# Main.net
KiCad netlist of a schematic drawn in Altium Designer
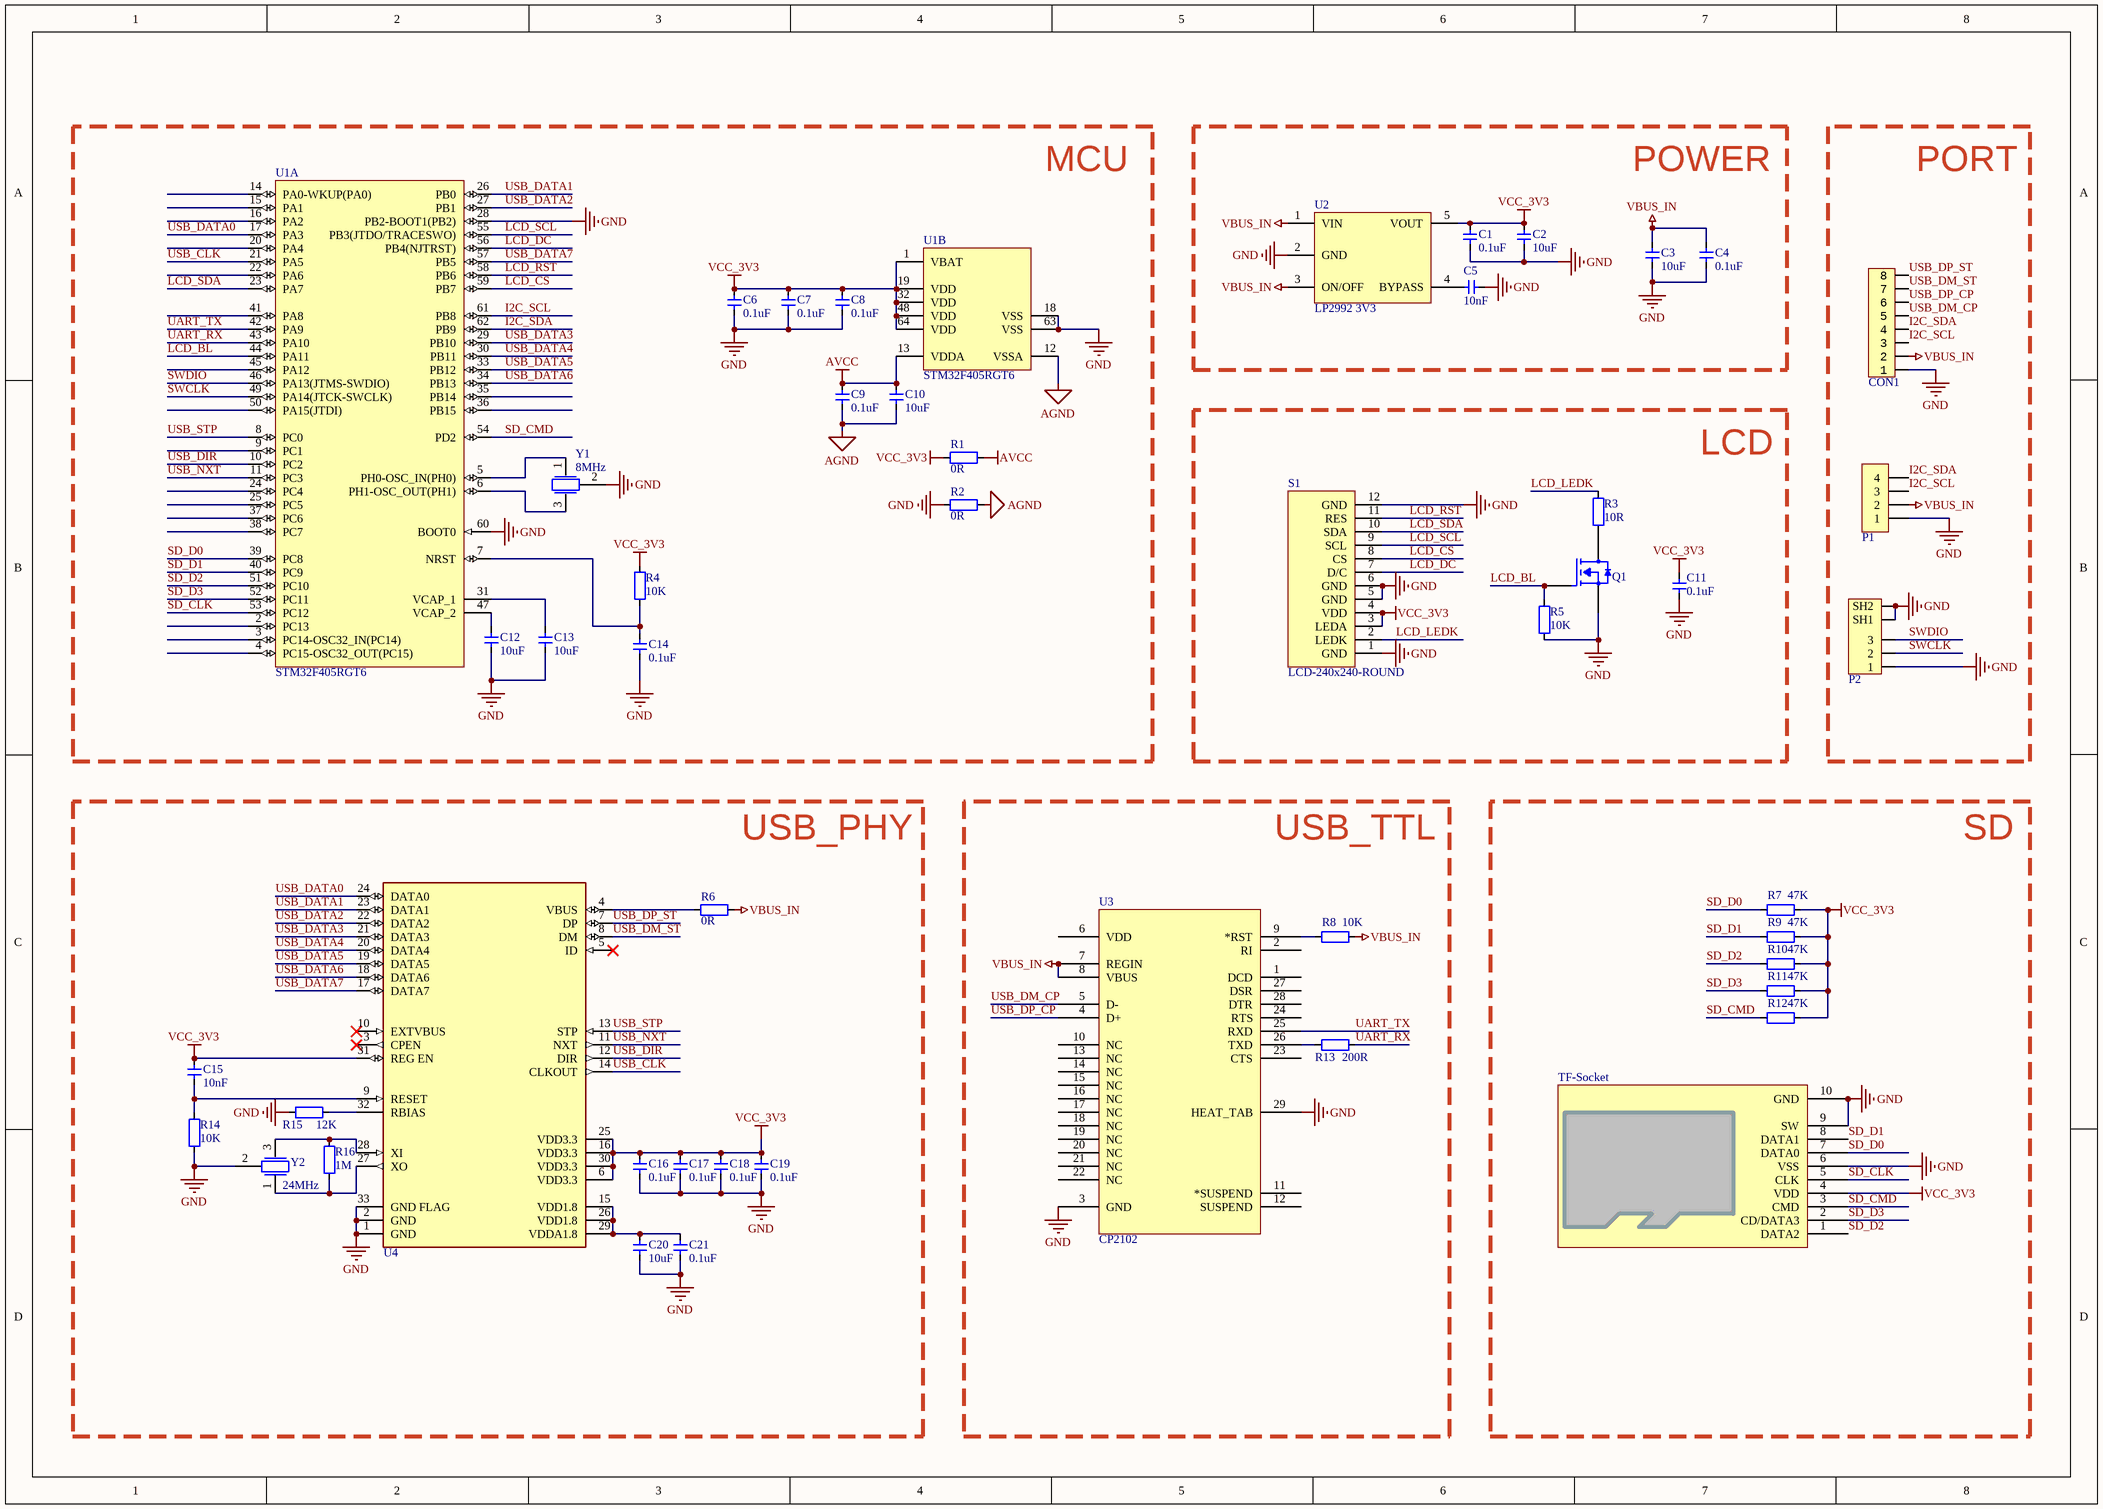
[diagram p0: Main.SchDoc]

(export (version "E")
  (design (tool "Eeschema 10.0.6"))
  (components
    (comp (ref "C1")
      (value "0.1uF")
      (footprint "CAP_0402")
      (description "Capacitor")
      (libsource (lib "MyPcbLib") (part "电容-0402"))
    )
    (comp (ref "C2")
      (value "10uF")
      (footprint "CAP_0402")
      (description "Capacitor")
      (libsource (lib "MyPcbLib") (part "电容-0402"))
    )
    (comp (ref "C3")
      (value "10uF")
      (footprint "CAP_0402")
      (description "Capacitor")
      (libsource (lib "MyPcbLib") (part "电容-0402"))
    )
    (comp (ref "C4")
      (value "0.1uF")
      (footprint "CAP_0402")
      (description "Capacitor")
      (libsource (lib "MyPcbLib") (part "电容-0402"))
    )
    (comp (ref "C5")
      (value "10nF")
      (footprint "CAP_0402")
      (description "Capacitor")
      (libsource (lib "MyPcbLib") (part "电容-0402"))
    )
    (comp (ref "C6")
      (value "0.1uF")
      (footprint "CAP_0402")
      (description "Capacitor")
      (libsource (lib "MyPcbLib") (part "电容-0402"))
    )
    (comp (ref "C7")
      (value "0.1uF")
      (footprint "CAP_0402")
      (description "Capacitor")
      (libsource (lib "MyPcbLib") (part "电容-0402"))
    )
    (comp (ref "C8")
      (value "0.1uF")
      (footprint "CAP_0402")
      (description "Capacitor")
      (libsource (lib "MyPcbLib") (part "电容-0402"))
    )
    (comp (ref "C9")
      (value "0.1uF")
      (footprint "CAP_0402")
      (description "Capacitor")
      (libsource (lib "MyPcbLib") (part "电容-0402"))
    )
    (comp (ref "C10")
      (value "10uF")
      (footprint "CAP_0402")
      (description "Capacitor")
      (libsource (lib "MyPcbLib") (part "电容-0402"))
    )
    (comp (ref "C11")
      (value "0.1uF")
      (footprint "CAP_0402")
      (description "Capacitor")
      (libsource (lib "MyPcbLib") (part "电容-0402"))
    )
    (comp (ref "C12")
      (value "10uF")
      (footprint "CAP_0402")
      (description "Capacitor")
      (libsource (lib "MyPcbLib") (part "电容-0402"))
    )
    (comp (ref "C13")
      (value "10uF")
      (footprint "CAP_0402")
      (description "Capacitor")
      (libsource (lib "MyPcbLib") (part "电容-0402"))
    )
    (comp (ref "C14")
      (value "0.1uF")
      (footprint "CAP_0402")
      (description "Capacitor")
      (libsource (lib "MyPcbLib") (part "电容-0402"))
    )
    (comp (ref "C15")
      (value "10nF")
      (footprint "CAP_0402")
      (description "Capacitor")
      (libsource (lib "MyPcbLib") (part "电容-0402"))
    )
    (comp (ref "C16")
      (value "0.1uF")
      (footprint "CAP_0402")
      (description "Capacitor")
      (libsource (lib "MyPcbLib") (part "电容-0402"))
    )
    (comp (ref "C17")
      (value "0.1uF")
      (footprint "CAP_0402")
      (description "Capacitor")
      (libsource (lib "MyPcbLib") (part "电容-0402"))
    )
    (comp (ref "C18")
      (value "0.1uF")
      (footprint "CAP_0402")
      (description "Capacitor")
      (libsource (lib "MyPcbLib") (part "电容-0402"))
    )
    (comp (ref "C19")
      (value "0.1uF")
      (footprint "CAP_0402")
      (description "Capacitor")
      (libsource (lib "MyPcbLib") (part "电容-0402"))
    )
    (comp (ref "C20")
      (value "10uF")
      (footprint "CAP_0402")
      (description "Capacitor")
      (libsource (lib "MyPcbLib") (part "电容-0402"))
    )
    (comp (ref "C21")
      (value "0.1uF")
      (footprint "CAP_0402")
      (description "Capacitor")
      (libsource (lib "MyPcbLib") (part "电容-0402"))
    )
    (comp (ref "CON1")
      (value "FFC_0.5_8")
      (footprint "FFC_0.5_8")
      (description "FFC")
      (libsource (lib "KitSprout") (part "FFC_0.5_8"))
    )
    (comp (ref "P1")
      (value "CON-4P")
      (footprint "FPC0.5-WT-4P")
      (description "4P连接器")
      (libsource (lib "4.9 - 0.5mm连接器(FPC0.5)") (part "Header 4"))
    )
    (comp (ref "P2")
      (value "SH1.0-3P-STAND")
      (footprint "SH1.0-3P-STAND")
      (description "Header")
      (libsource (lib "MyPcbLib") (part "SH1.0-3P-STAND"))
    )
    (comp (ref "Q1")
      (value "AO3400A")
      (footprint "SOT23-3")
      (description "N-MOS")
      (libsource (lib "MyPcbLib") (part "AO3400A"))
    )
    (comp (ref "R1")
      (value "0R")
      (footprint "RES_0402")
      (description "Resistor")
      (libsource (lib "MyPcbLib") (part "电阻-0402"))
    )
    (comp (ref "R2")
      (value "0R")
      (footprint "RES_0402")
      (description "Resistor")
      (libsource (lib "MyPcbLib") (part "电阻-0402"))
    )
    (comp (ref "R3")
      (value "10R")
      (footprint "RES_0402")
      (description "Resistor")
      (libsource (lib "") (part "电阻-0402_1"))
    )
    (comp (ref "R4")
      (value "10K")
      (footprint "RES_0402")
      (description "Resistor")
      (libsource (lib "") (part "电阻-0402_1"))
    )
    (comp (ref "R5")
      (value "10K")
      (footprint "RES_0402")
      (description "Resistor")
      (libsource (lib "") (part "电阻-0402_1"))
    )
    (comp (ref "R6")
      (value "0R")
      (footprint "RES_0402")
      (description "Resistor")
      (libsource (lib "MyPcbLib") (part "电阻-0402"))
    )
    (comp (ref "R7")
      (value "47K")
      (footprint "RES_0402")
      (description "Resistor")
      (libsource (lib "MyPcbLib") (part "电阻-0402"))
    )
    (comp (ref "R8")
      (value "10K")
      (footprint "RES_0402")
      (description "Resistor")
      (libsource (lib "MyPcbLib") (part "电阻-0402"))
    )
    (comp (ref "R9")
      (value "47K")
      (footprint "RES_0402")
      (description "Resistor")
      (libsource (lib "MyPcbLib") (part "电阻-0402"))
    )
    (comp (ref "R10")
      (value "47K")
      (footprint "RES_0402")
      (description "Resistor")
      (libsource (lib "MyPcbLib") (part "电阻-0402"))
    )
    (comp (ref "R11")
      (value "47K")
      (footprint "RES_0402")
      (description "Resistor")
      (libsource (lib "MyPcbLib") (part "电阻-0402"))
    )
    (comp (ref "R12")
      (value "47K")
      (footprint "RES_0402")
      (description "Resistor")
      (libsource (lib "MyPcbLib") (part "电阻-0402"))
    )
    (comp (ref "R13")
      (value "200R")
      (footprint "RES_0402")
      (description "Resistor")
      (libsource (lib "MyPcbLib") (part "电阻-0402"))
    )
    (comp (ref "R14")
      (value "10K")
      (footprint "RES_0402")
      (description "Resistor")
      (libsource (lib "") (part "电阻-0402_2"))
    )
    (comp (ref "R15")
      (value "12K")
      (footprint "RES_0402")
      (description "Resistor")
      (libsource (lib "MyPcbLib") (part "电阻-0402"))
    )
    (comp (ref "R16")
      (value "1M")
      (footprint "RES_0402")
      (description "Resistor")
      (libsource (lib "") (part "电阻-0402_2"))
    )
    (comp (ref "S1")
      (value "LCD-240x240-ROUND")
      (footprint "LCD-240x240-ROUND")
      (description "显示屏")
      (libsource (lib "mLib") (part "LCD-240x240-ROUND"))
    )
    (comp (ref "TF-Socket")
      (value "TF")
      (footprint "TF-Card-Amphenol with TF")
      (description "8脚自弹")
      (libsource (lib "MyPcbLib") (part "TF卡座"))
    )
    (comp (ref "U1")
      (value "STM32F405RGT6")
      (footprint "LQFP-64_N")
      (fields (field (name "MANUFACTURER") "STMicroelectronics"))
      (libsource (lib "STMicroelectronics STM32 F4") (part "STM32F405RGT6"))
    )
    (comp (ref "U2")
      (value "LP2992 3V3")
      (footprint "SOT23-5")
      (description "LDO")
      (libsource (lib "MyPcbLib") (part "LP2992"))
    )
    (comp (ref "U3")
      (value "CP2102")
      (footprint "QFN-28")
      (description "USB转TTL")
      (libsource (lib "mLib") (part "CP2102"))
    )
    (comp (ref "U4")
      (value "USB3300-EZK-TR")
      (footprint "QFN-32")
      (libsource (lib "mLib") (part "USB3300-EZK-TR"))
    )
    (comp (ref "Y1")
      (value "8MHz")
      (footprint "晶振-3P")
      (description "村田贴片")
      (libsource (lib "MyPcbLib") (part "晶振-3Pin"))
    )
    (comp (ref "Y2")
      (value "24MHz")
      (footprint "晶振-3P")
      (description "村田贴片")
      (libsource (lib "MyPcbLib") (part "晶振-3Pin"))
    )
  )
  (nets
    (net (code "1") (name "/I2C_SCL") (class "Default")
      (node (ref "CON1") (pin "3") (pinfunction "3_3") (pintype "passive"))
      (node (ref "P1") (pin "3") (pinfunction "3_3") (pintype "passive"))
      (node (ref "U1") (pin "61") (pinfunction "PB8_61") (pintype "bidirectional"))
    )
    (net (code "2") (name "/I2C_SDA") (class "Default")
      (node (ref "CON1") (pin "4") (pinfunction "4_4") (pintype "passive"))
      (node (ref "P1") (pin "4") (pinfunction "4_4") (pintype "passive"))
      (node (ref "U1") (pin "62") (pinfunction "PB9_62") (pintype "bidirectional"))
    )
    (net (code "3") (name "/LCD_BL") (class "Default")
      (node (ref "Q1") (pin "1") (pinfunction "G_1") (pintype "passive"))
      (node (ref "R5") (pin "2") (pinfunction "2_2") (pintype "passive"))
      (node (ref "U1") (pin "44") (pinfunction "PA11_44") (pintype "bidirectional"))
    )
    (net (code "4") (name "/LCD_CS") (class "Default")
      (node (ref "S1") (pin "8") (pinfunction "CS_8") (pintype "passive"))
      (node (ref "U1") (pin "59") (pinfunction "PB7_59") (pintype "bidirectional"))
    )
    (net (code "5") (name "/LCD_DC") (class "Default")
      (node (ref "S1") (pin "7") (pinfunction "D/C_7") (pintype "passive"))
      (node (ref "U1") (pin "56") (pinfunction "PB4(NJTRST)_56") (pintype "bidirectional"))
    )
    (net (code "6") (name "/LCD_LEDK") (class "Default")
      (node (ref "R3") (pin "2") (pinfunction "2_2") (pintype "passive"))
      (node (ref "S1") (pin "2") (pinfunction "LEDK_2") (pintype "passive"))
    )
    (net (code "7") (name "/LCD_RST") (class "Default")
      (node (ref "S1") (pin "11") (pinfunction "RES_11") (pintype "passive"))
      (node (ref "U1") (pin "58") (pinfunction "PB6_58") (pintype "bidirectional"))
    )
    (net (code "8") (name "/LCD_SCL") (class "Default")
      (node (ref "S1") (pin "9") (pinfunction "SCL_9") (pintype "passive"))
      (node (ref "U1") (pin "55") (pinfunction "PB3(JTDO/TRACESWO)_55") (pintype "bidirectional"))
    )
    (net (code "9") (name "/LCD_SDA") (class "Default")
      (node (ref "S1") (pin "10") (pinfunction "SDA_10") (pintype "passive"))
      (node (ref "U1") (pin "23") (pinfunction "PA7_23") (pintype "bidirectional"))
    )
    (net (code "10") (name "/SD_CLK") (class "Default")
      (node (ref "TF-Socket") (pin "5") (pinfunction "CLK_5") (pintype "passive"))
      (node (ref "U1") (pin "53") (pinfunction "PC12_53") (pintype "bidirectional"))
    )
    (net (code "11") (name "/SD_CMD") (class "Default")
      (node (ref "R12") (pin "2") (pinfunction "2_2") (pintype "passive"))
      (node (ref "TF-Socket") (pin "3") (pinfunction "CMD_3") (pintype "passive"))
      (node (ref "U1") (pin "54") (pinfunction "PD2_54") (pintype "bidirectional"))
    )
    (net (code "12") (name "/SD_D0") (class "Default")
      (node (ref "R7") (pin "2") (pinfunction "2_2") (pintype "passive"))
      (node (ref "TF-Socket") (pin "7") (pinfunction "DATA0_7") (pintype "passive"))
      (node (ref "U1") (pin "39") (pinfunction "PC8_39") (pintype "bidirectional"))
    )
    (net (code "13") (name "/SD_D1") (class "Default")
      (node (ref "R9") (pin "2") (pinfunction "2_2") (pintype "passive"))
      (node (ref "TF-Socket") (pin "8") (pinfunction "DATA1_8") (pintype "passive"))
      (node (ref "U1") (pin "40") (pinfunction "PC9_40") (pintype "bidirectional"))
    )
    (net (code "14") (name "/SD_D2") (class "Default")
      (node (ref "R10") (pin "2") (pinfunction "2_2") (pintype "passive"))
      (node (ref "TF-Socket") (pin "1") (pinfunction "DATA2_1") (pintype "passive"))
      (node (ref "U1") (pin "51") (pinfunction "PC10_51") (pintype "bidirectional"))
    )
    (net (code "15") (name "/SD_D3") (class "Default")
      (node (ref "R11") (pin "2") (pinfunction "2_2") (pintype "passive"))
      (node (ref "TF-Socket") (pin "2") (pinfunction "CD/DATA3_2") (pintype "passive"))
      (node (ref "U1") (pin "52") (pinfunction "PC11_52") (pintype "bidirectional"))
    )
    (net (code "16") (name "/SWCLK") (class "Default")
      (node (ref "P2") (pin "2") (pinfunction "2_2") (pintype "passive"))
      (node (ref "U1") (pin "49") (pinfunction "PA14(JTCK-SWCLK)_49") (pintype "bidirectional"))
    )
    (net (code "17") (name "/SWDIO") (class "Default")
      (node (ref "P2") (pin "3") (pinfunction "3_3") (pintype "passive"))
      (node (ref "U1") (pin "46") (pinfunction "PA13(JTMS-SWDIO)_46") (pintype "bidirectional"))
    )
    (net (code "18") (name "/UART_RX") (class "Default")
      (node (ref "R13") (pin "1") (pinfunction "1_1") (pintype "passive"))
      (node (ref "U1") (pin "43") (pinfunction "PA10_43") (pintype "bidirectional"))
    )
    (net (code "19") (name "/UART_TX") (class "Default")
      (node (ref "U1") (pin "42") (pinfunction "PA9_42") (pintype "bidirectional"))
      (node (ref "U3") (pin "25") (pinfunction "RXD_25") (pintype "passive"))
    )
    (net (code "20") (name "/USB_CLK") (class "Default")
      (node (ref "U1") (pin "21") (pinfunction "PA5_21") (pintype "bidirectional"))
      (node (ref "U4") (pin "14") (pinfunction "CLKOUT_14") (pintype "output"))
    )
    (net (code "21") (name "/USB_DATA0") (class "Default")
      (node (ref "U1") (pin "17") (pinfunction "PA3_17") (pintype "bidirectional"))
      (node (ref "U4") (pin "24") (pinfunction "DATA0_24") (pintype "bidirectional"))
    )
    (net (code "22") (name "/USB_DATA1") (class "Default")
      (node (ref "U1") (pin "26") (pinfunction "PB0_26") (pintype "bidirectional"))
      (node (ref "U4") (pin "23") (pinfunction "DATA1_23") (pintype "bidirectional"))
    )
    (net (code "23") (name "/USB_DATA2") (class "Default")
      (node (ref "U1") (pin "27") (pinfunction "PB1_27") (pintype "bidirectional"))
      (node (ref "U4") (pin "22") (pinfunction "DATA2_22") (pintype "bidirectional"))
    )
    (net (code "24") (name "/USB_DATA3") (class "Default")
      (node (ref "U1") (pin "29") (pinfunction "PB10_29") (pintype "bidirectional"))
      (node (ref "U4") (pin "21") (pinfunction "DATA3_21") (pintype "bidirectional"))
    )
    (net (code "25") (name "/USB_DATA4") (class "Default")
      (node (ref "U1") (pin "30") (pinfunction "PB11_30") (pintype "bidirectional"))
      (node (ref "U4") (pin "20") (pinfunction "DATA4_20") (pintype "bidirectional"))
    )
    (net (code "26") (name "/USB_DATA5") (class "Default")
      (node (ref "U1") (pin "33") (pinfunction "PB12_33") (pintype "bidirectional"))
      (node (ref "U4") (pin "19") (pinfunction "DATA5_19") (pintype "bidirectional"))
    )
    (net (code "27") (name "/USB_DATA6") (class "Default")
      (node (ref "U1") (pin "34") (pinfunction "PB13_34") (pintype "bidirectional"))
      (node (ref "U4") (pin "18") (pinfunction "DATA6_18") (pintype "bidirectional"))
    )
    (net (code "28") (name "/USB_DATA7") (class "Default")
      (node (ref "U1") (pin "57") (pinfunction "PB5_57") (pintype "bidirectional"))
      (node (ref "U4") (pin "17") (pinfunction "DATA7_17") (pintype "bidirectional"))
    )
    (net (code "29") (name "/USB_DIR") (class "Default")
      (node (ref "U1") (pin "10") (pinfunction "PC2_10") (pintype "bidirectional"))
      (node (ref "U4") (pin "12") (pinfunction "DIR_12") (pintype "output"))
    )
    (net (code "30") (name "/USB_DM_CP") (class "Default")
      (node (ref "CON1") (pin "5") (pinfunction "5_5") (pintype "passive"))
      (node (ref "U3") (pin "5") (pinfunction "D-_5") (pintype "passive"))
    )
    (net (code "31") (name "/USB_DM_ST") (class "Default")
      (node (ref "CON1") (pin "7") (pinfunction "7_7") (pintype "passive"))
      (node (ref "U4") (pin "8") (pinfunction "DM_8") (pintype "bidirectional"))
    )
    (net (code "32") (name "/USB_DP_CP") (class "Default")
      (node (ref "CON1") (pin "6") (pinfunction "6_6") (pintype "passive"))
      (node (ref "U3") (pin "4") (pinfunction "D+_4") (pintype "passive"))
    )
    (net (code "33") (name "/USB_DP_ST") (class "Default")
      (node (ref "CON1") (pin "8") (pinfunction "8_8") (pintype "passive"))
      (node (ref "U4") (pin "7") (pinfunction "DP_7") (pintype "bidirectional"))
    )
    (net (code "34") (name "/USB_NXT") (class "Default")
      (node (ref "U1") (pin "11") (pinfunction "PC3_11") (pintype "bidirectional"))
      (node (ref "U4") (pin "11") (pinfunction "NXT_11") (pintype "output"))
    )
    (net (code "35") (name "/USB_STP") (class "Default")
      (node (ref "U1") (pin "8") (pinfunction "PC0_8") (pintype "bidirectional"))
      (node (ref "U4") (pin "13") (pinfunction "STP_13") (pintype "input"))
    )
    (net (code "36") (name "AGND") (class "Default")
      (node (ref "C10") (pin "1") (pinfunction "1_1") (pintype "passive"))
      (node (ref "C9") (pin "1") (pinfunction "1_1") (pintype "passive"))
      (node (ref "R2") (pin "1") (pinfunction "1_1") (pintype "passive"))
      (node (ref "U1") (pin "12") (pinfunction "VSSA_12") (pintype "power_in"))
    )
    (net (code "37") (name "AVCC") (class "Default")
      (node (ref "C10") (pin "2") (pinfunction "2_2") (pintype "passive"))
      (node (ref "C9") (pin "2") (pinfunction "2_2") (pintype "passive"))
      (node (ref "R1") (pin "1") (pinfunction "1_1") (pintype "passive"))
      (node (ref "U1") (pin "13") (pinfunction "VDDA_13") (pintype "power_in"))
    )
    (net (code "38") (name "GND") (class "Default")
      (node (ref "C1") (pin "1") (pinfunction "1_1") (pintype "passive"))
      (node (ref "C11") (pin "1") (pinfunction "1_1") (pintype "passive"))
      (node (ref "C12") (pin "1") (pinfunction "1_1") (pintype "passive"))
      (node (ref "C13") (pin "1") (pinfunction "1_1") (pintype "passive"))
      (node (ref "C14") (pin "1") (pinfunction "1_1") (pintype "passive"))
      (node (ref "C16") (pin "2") (pinfunction "2_2") (pintype "passive"))
      (node (ref "C17") (pin "2") (pinfunction "2_2") (pintype "passive"))
      (node (ref "C18") (pin "2") (pinfunction "2_2") (pintype "passive"))
      (node (ref "C19") (pin "2") (pinfunction "2_2") (pintype "passive"))
      (node (ref "C2") (pin "1") (pinfunction "1_1") (pintype "passive"))
      (node (ref "C20") (pin "2") (pinfunction "2_2") (pintype "passive"))
      (node (ref "C21") (pin "2") (pinfunction "2_2") (pintype "passive"))
      (node (ref "C3") (pin "1") (pinfunction "1_1") (pintype "passive"))
      (node (ref "C4") (pin "1") (pinfunction "1_1") (pintype "passive"))
      (node (ref "C5") (pin "1") (pinfunction "1_1") (pintype "passive"))
      (node (ref "C6") (pin "1") (pinfunction "1_1") (pintype "passive"))
      (node (ref "C7") (pin "1") (pinfunction "1_1") (pintype "passive"))
      (node (ref "C8") (pin "1") (pinfunction "1_1") (pintype "passive"))
      (node (ref "CON1") (pin "1") (pinfunction "1_1") (pintype "passive"))
      (node (ref "P1") (pin "1") (pinfunction "1_1") (pintype "passive"))
      (node (ref "P2") (pin "1") (pinfunction "1_1") (pintype "passive"))
      (node (ref "P2") (pin "SH1") (pinfunction "SH1_SH1") (pintype "passive"))
      (node (ref "P2") (pin "SH2") (pinfunction "SH2_SH2") (pintype "passive"))
      (node (ref "Q1") (pin "2") (pinfunction "S_2") (pintype "passive"))
      (node (ref "R14") (pin "2") (pinfunction "2_2") (pintype "passive"))
      (node (ref "R15") (pin "2") (pinfunction "2_2") (pintype "passive"))
      (node (ref "R2") (pin "2") (pinfunction "2_2") (pintype "passive"))
      (node (ref "R5") (pin "1") (pinfunction "1_1") (pintype "passive"))
      (node (ref "S1") (pin "1") (pinfunction "GND_1") (pintype "passive"))
      (node (ref "S1") (pin "12") (pinfunction "GND_12") (pintype "passive"))
      (node (ref "S1") (pin "5") (pinfunction "GND_5") (pintype "passive"))
      (node (ref "S1") (pin "6") (pinfunction "GND_6") (pintype "passive"))
      (node (ref "TF-Socket") (pin "10") (pinfunction "GND_10") (pintype "passive"))
      (node (ref "TF-Socket") (pin "6") (pinfunction "VSS_6") (pintype "passive"))
      (node (ref "TF-Socket") (pin "9") (pinfunction "SW_9") (pintype "passive"))
      (node (ref "U1") (pin "18") (pinfunction "VSS_18") (pintype "power_in"))
      (node (ref "U1") (pin "28") (pinfunction "PB2-BOOT1(PB2)_28") (pintype "bidirectional"))
      (node (ref "U1") (pin "60") (pinfunction "BOOT0_60") (pintype "input"))
      (node (ref "U1") (pin "63") (pinfunction "VSS_63") (pintype "power_in"))
      (node (ref "U2") (pin "2") (pinfunction "GND_2") (pintype "passive"))
      (node (ref "U3") (pin "29") (pinfunction "HEAT_TAB_29") (pintype "passive"))
      (node (ref "U3") (pin "3") (pinfunction "GND_3") (pintype "passive"))
      (node (ref "U4") (pin "1") (pinfunction "GND_1") (pintype "power_in"))
      (node (ref "U4") (pin "2") (pinfunction "GND_2") (pintype "power_in"))
      (node (ref "U4") (pin "33") (pinfunction "GND_FLAG_33") (pintype "power_in"))
      (node (ref "Y1") (pin "2") (pinfunction "2_2") (pintype "passive"))
      (node (ref "Y2") (pin "2") (pinfunction "2_2") (pintype "passive"))
    )
    (net (code "39") (name "Net-(Q1-D)") (class "Default")
      (node (ref "Q1") (pin "3") (pinfunction "D_3") (pintype "passive"))
      (node (ref "R3") (pin "1") (pinfunction "1_1") (pintype "passive"))
    )
    (net (code "40") (name "Net-(U1A-NRST)") (class "Default")
      (node (ref "C14") (pin "2") (pinfunction "2_2") (pintype "passive"))
      (node (ref "R4") (pin "1") (pinfunction "1_1") (pintype "passive"))
      (node (ref "U1") (pin "7") (pinfunction "NRST_7") (pintype "bidirectional"))
    )
    (net (code "41") (name "Net-(U1A-PH0-OSC_IN(PH0))") (class "Default")
      (node (ref "U1") (pin "5") (pinfunction "PH0-OSC_IN(PH0)_5") (pintype "bidirectional"))
      (node (ref "Y1") (pin "1") (pinfunction "1_1") (pintype "passive"))
    )
    (net (code "42") (name "Net-(U1A-PH1-OSC_OUT(PH1))") (class "Default")
      (node (ref "U1") (pin "6") (pinfunction "PH1-OSC_OUT(PH1)_6") (pintype "bidirectional"))
      (node (ref "Y1") (pin "3") (pinfunction "3_3") (pintype "passive"))
    )
    (net (code "43") (name "Net-(U1A-VCAP_1)") (class "Default")
      (node (ref "C13") (pin "2") (pinfunction "2_2") (pintype "passive"))
      (node (ref "U1") (pin "31") (pinfunction "VCAP_1_31") (pintype "power_in"))
    )
    (net (code "44") (name "Net-(U1A-VCAP_2)") (class "Default")
      (node (ref "C12") (pin "2") (pinfunction "2_2") (pintype "passive"))
      (node (ref "U1") (pin "47") (pinfunction "VCAP_2_47") (pintype "power_in"))
    )
    (net (code "45") (name "Net-(U2-BYPASS)") (class "Default")
      (node (ref "C5") (pin "2") (pinfunction "2_2") (pintype "passive"))
      (node (ref "U2") (pin "4") (pinfunction "BYPASS_4") (pintype "passive"))
    )
    (net (code "46") (name "Net-(U3-*RST)") (class "Default")
      (node (ref "R8") (pin "2") (pinfunction "2_2") (pintype "passive"))
      (node (ref "U3") (pin "9") (pinfunction "*RST_9") (pintype "passive"))
    )
    (net (code "47") (name "Net-(U3-TXD)") (class "Default")
      (node (ref "R13") (pin "2") (pinfunction "2_2") (pintype "passive"))
      (node (ref "U3") (pin "26") (pinfunction "TXD_26") (pintype "passive"))
    )
    (net (code "48") (name "Net-(U4-RBIAS)") (class "Default")
      (node (ref "R15") (pin "1") (pinfunction "1_1") (pintype "passive"))
      (node (ref "U4") (pin "32") (pinfunction "RBIAS_32") (pintype "power_in"))
    )
    (net (code "49") (name "Net-(U4-RESET)") (class "Default")
      (node (ref "C15") (pin "2") (pinfunction "2_2") (pintype "passive"))
      (node (ref "R14") (pin "1") (pinfunction "1_1") (pintype "passive"))
      (node (ref "U4") (pin "9") (pinfunction "RESET_9") (pintype "input"))
    )
    (net (code "50") (name "Net-(U4-VBUS)") (class "Default")
      (node (ref "R6") (pin "2") (pinfunction "2_2") (pintype "passive"))
      (node (ref "U4") (pin "4") (pinfunction "VBUS_4") (pintype "bidirectional"))
    )
    (net (code "51") (name "Net-(U4-VDDA1.8)") (class "Default")
      (node (ref "C20") (pin "1") (pinfunction "1_1") (pintype "passive"))
      (node (ref "C21") (pin "1") (pinfunction "1_1") (pintype "passive"))
      (node (ref "U4") (pin "15") (pinfunction "VDD1.8_15") (pintype "power_in"))
      (node (ref "U4") (pin "26") (pinfunction "VDD1.8_26") (pintype "power_in"))
      (node (ref "U4") (pin "29") (pinfunction "VDDA1.8_29") (pintype "power_in"))
    )
    (net (code "52") (name "Net-(U4-XI)") (class "Default")
      (node (ref "R16") (pin "1") (pinfunction "1_1") (pintype "passive"))
      (node (ref "U4") (pin "28") (pinfunction "XI_28") (pintype "input"))
      (node (ref "Y2") (pin "3") (pinfunction "3_3") (pintype "passive"))
    )
    (net (code "53") (name "Net-(U4-XO)") (class "Default")
      (node (ref "R16") (pin "2") (pinfunction "2_2") (pintype "passive"))
      (node (ref "U4") (pin "27") (pinfunction "XO_27") (pintype "output"))
      (node (ref "Y2") (pin "1") (pinfunction "1_1") (pintype "passive"))
    )
    (net (code "54") (name "VBUS_IN") (class "Default")
      (node (ref "C3") (pin "2") (pinfunction "2_2") (pintype "passive"))
      (node (ref "C4") (pin "2") (pinfunction "2_2") (pintype "passive"))
      (node (ref "CON1") (pin "2") (pinfunction "2_2") (pintype "passive"))
      (node (ref "P1") (pin "2") (pinfunction "2_2") (pintype "passive"))
      (node (ref "R6") (pin "1") (pinfunction "1_1") (pintype "passive"))
      (node (ref "R8") (pin "1") (pinfunction "1_1") (pintype "passive"))
      (node (ref "U2") (pin "1") (pinfunction "VIN_1") (pintype "passive"))
      (node (ref "U2") (pin "3") (pinfunction "ON/OFF_3") (pintype "passive"))
      (node (ref "U3") (pin "7") (pinfunction "REGIN_7") (pintype "passive"))
      (node (ref "U3") (pin "8") (pinfunction "VBUS_8") (pintype "passive"))
    )
    (net (code "55") (name "VCC_3V3") (class "Default")
      (node (ref "C1") (pin "2") (pinfunction "2_2") (pintype "passive"))
      (node (ref "C11") (pin "2") (pinfunction "2_2") (pintype "passive"))
      (node (ref "C15") (pin "1") (pinfunction "1_1") (pintype "passive"))
      (node (ref "C16") (pin "1") (pinfunction "1_1") (pintype "passive"))
      (node (ref "C17") (pin "1") (pinfunction "1_1") (pintype "passive"))
      (node (ref "C18") (pin "1") (pinfunction "1_1") (pintype "passive"))
      (node (ref "C19") (pin "1") (pinfunction "1_1") (pintype "passive"))
      (node (ref "C2") (pin "2") (pinfunction "2_2") (pintype "passive"))
      (node (ref "C6") (pin "2") (pinfunction "2_2") (pintype "passive"))
      (node (ref "C7") (pin "2") (pinfunction "2_2") (pintype "passive"))
      (node (ref "C8") (pin "2") (pinfunction "2_2") (pintype "passive"))
      (node (ref "R1") (pin "2") (pinfunction "2_2") (pintype "passive"))
      (node (ref "R10") (pin "1") (pinfunction "1_1") (pintype "passive"))
      (node (ref "R11") (pin "1") (pinfunction "1_1") (pintype "passive"))
      (node (ref "R12") (pin "1") (pinfunction "1_1") (pintype "passive"))
      (node (ref "R4") (pin "2") (pinfunction "2_2") (pintype "passive"))
      (node (ref "R7") (pin "1") (pinfunction "1_1") (pintype "passive"))
      (node (ref "R9") (pin "1") (pinfunction "1_1") (pintype "passive"))
      (node (ref "S1") (pin "3") (pinfunction "LEDA_3") (pintype "passive"))
      (node (ref "S1") (pin "4") (pinfunction "VDD_4") (pintype "passive"))
      (node (ref "TF-Socket") (pin "4") (pinfunction "VDD_4") (pintype "passive"))
      (node (ref "U1") (pin "1") (pinfunction "VBAT_1") (pintype "power_in"))
      (node (ref "U1") (pin "19") (pinfunction "VDD_19") (pintype "power_in"))
      (node (ref "U1") (pin "32") (pinfunction "VDD_32") (pintype "power_in"))
      (node (ref "U1") (pin "48") (pinfunction "VDD_48") (pintype "power_in"))
      (node (ref "U1") (pin "64") (pinfunction "VDD_64") (pintype "power_in"))
      (node (ref "U2") (pin "5") (pinfunction "VOUT_5") (pintype "passive"))
      (node (ref "U4") (pin "16") (pinfunction "VDD3.3_16") (pintype "power_in"))
      (node (ref "U4") (pin "25") (pinfunction "VDD3.3_25") (pintype "power_in"))
      (node (ref "U4") (pin "30") (pinfunction "VDD3.3_30") (pintype "power_in"))
      (node (ref "U4") (pin "31") (pinfunction "REG_EN_31") (pintype "bidirectional"))
      (node (ref "U4") (pin "6") (pinfunction "VDD3.3_6") (pintype "power_in"))
    )
    (net (code "56") (name "unconnected-(U1A-PA0-WKUP(PA0)-Pad14)") (class "Default")
      (node (ref "U1") (pin "14") (pinfunction "PA0-WKUP(PA0)_14") (pintype "bidirectional"))
    )
    (net (code "57") (name "unconnected-(U1A-PA1-Pad15)") (class "Default")
      (node (ref "U1") (pin "15") (pinfunction "PA1_15") (pintype "bidirectional"))
    )
    (net (code "58") (name "unconnected-(U1A-PA2-Pad16)") (class "Default")
      (node (ref "U1") (pin "16") (pinfunction "PA2_16") (pintype "bidirectional"))
    )
    (net (code "59") (name "unconnected-(U1A-PA4-Pad20)") (class "Default")
      (node (ref "U1") (pin "20") (pinfunction "PA4_20") (pintype "bidirectional"))
    )
    (net (code "60") (name "unconnected-(U1A-PA6-Pad22)") (class "Default")
      (node (ref "U1") (pin "22") (pinfunction "PA6_22") (pintype "bidirectional"))
    )
    (net (code "61") (name "unconnected-(U1A-PA8-Pad41)") (class "Default")
      (node (ref "U1") (pin "41") (pinfunction "PA8_41") (pintype "bidirectional"))
    )
    (net (code "62") (name "unconnected-(U1A-PA12-Pad45)") (class "Default")
      (node (ref "U1") (pin "45") (pinfunction "PA12_45") (pintype "bidirectional"))
    )
    (net (code "63") (name "unconnected-(U1A-PA15(JTDI)-Pad50)") (class "Default")
      (node (ref "U1") (pin "50") (pinfunction "PA15(JTDI)_50") (pintype "bidirectional"))
    )
    (net (code "64") (name "unconnected-(U1A-PB14-Pad35)") (class "Default")
      (node (ref "U1") (pin "35") (pinfunction "PB14_35") (pintype "bidirectional"))
    )
    (net (code "65") (name "unconnected-(U1A-PB15-Pad36)") (class "Default")
      (node (ref "U1") (pin "36") (pinfunction "PB15_36") (pintype "bidirectional"))
    )
    (net (code "66") (name "unconnected-(U1A-PC1-Pad9)") (class "Default")
      (node (ref "U1") (pin "9") (pinfunction "PC1_9") (pintype "bidirectional"))
    )
    (net (code "67") (name "unconnected-(U1A-PC4-Pad24)") (class "Default")
      (node (ref "U1") (pin "24") (pinfunction "PC4_24") (pintype "bidirectional"))
    )
    (net (code "68") (name "unconnected-(U1A-PC5-Pad25)") (class "Default")
      (node (ref "U1") (pin "25") (pinfunction "PC5_25") (pintype "bidirectional"))
    )
    (net (code "69") (name "unconnected-(U1A-PC6-Pad37)") (class "Default")
      (node (ref "U1") (pin "37") (pinfunction "PC6_37") (pintype "bidirectional"))
    )
    (net (code "70") (name "unconnected-(U1A-PC7-Pad38)") (class "Default")
      (node (ref "U1") (pin "38") (pinfunction "PC7_38") (pintype "bidirectional"))
    )
    (net (code "71") (name "unconnected-(U1A-PC13-Pad2)") (class "Default")
      (node (ref "U1") (pin "2") (pinfunction "PC13_2") (pintype "bidirectional"))
    )
    (net (code "72") (name "unconnected-(U1A-PC14-OSC32_IN(PC14)-Pad3)") (class "Default")
      (node (ref "U1") (pin "3") (pinfunction "PC14-OSC32_IN(PC14)_3") (pintype "bidirectional"))
    )
    (net (code "73") (name "unconnected-(U1A-PC15-OSC32_OUT(PC15)-Pad4)") (class "Default")
      (node (ref "U1") (pin "4") (pinfunction "PC15-OSC32_OUT(PC15)_4") (pintype "bidirectional"))
    )
    (net (code "74") (name "unconnected-(U3-*SUSPEND-Pad11)") (class "Default")
      (node (ref "U3") (pin "11") (pinfunction "*SUSPEND_11") (pintype "passive"))
    )
    (net (code "75") (name "unconnected-(U3-CTS-Pad23)") (class "Default")
      (node (ref "U3") (pin "23") (pinfunction "CTS_23") (pintype "passive"))
    )
    (net (code "76") (name "unconnected-(U3-DCD-Pad1)") (class "Default")
      (node (ref "U3") (pin "1") (pinfunction "DCD_1") (pintype "passive"))
    )
    (net (code "77") (name "unconnected-(U3-DSR-Pad27)") (class "Default")
      (node (ref "U3") (pin "27") (pinfunction "DSR_27") (pintype "passive"))
    )
    (net (code "78") (name "unconnected-(U3-DTR-Pad28)") (class "Default")
      (node (ref "U3") (pin "28") (pinfunction "DTR_28") (pintype "passive"))
    )
    (net (code "79") (name "unconnected-(U3-NC-Pad10)") (class "Default")
      (node (ref "U3") (pin "10") (pinfunction "NC_10") (pintype "passive"))
    )
    (net (code "80") (name "unconnected-(U3-NC-Pad13)") (class "Default")
      (node (ref "U3") (pin "13") (pinfunction "NC_13") (pintype "passive"))
    )
    (net (code "81") (name "unconnected-(U3-NC-Pad14)") (class "Default")
      (node (ref "U3") (pin "14") (pinfunction "NC_14") (pintype "passive"))
    )
    (net (code "82") (name "unconnected-(U3-NC-Pad15)") (class "Default")
      (node (ref "U3") (pin "15") (pinfunction "NC_15") (pintype "passive"))
    )
    (net (code "83") (name "unconnected-(U3-NC-Pad16)") (class "Default")
      (node (ref "U3") (pin "16") (pinfunction "NC_16") (pintype "passive"))
    )
    (net (code "84") (name "unconnected-(U3-NC-Pad17)") (class "Default")
      (node (ref "U3") (pin "17") (pinfunction "NC_17") (pintype "passive"))
    )
    (net (code "85") (name "unconnected-(U3-NC-Pad18)") (class "Default")
      (node (ref "U3") (pin "18") (pinfunction "NC_18") (pintype "passive"))
    )
    (net (code "86") (name "unconnected-(U3-NC-Pad19)") (class "Default")
      (node (ref "U3") (pin "19") (pinfunction "NC_19") (pintype "passive"))
    )
    (net (code "87") (name "unconnected-(U3-NC-Pad20)") (class "Default")
      (node (ref "U3") (pin "20") (pinfunction "NC_20") (pintype "passive"))
    )
    (net (code "88") (name "unconnected-(U3-NC-Pad21)") (class "Default")
      (node (ref "U3") (pin "21") (pinfunction "NC_21") (pintype "passive"))
    )
    (net (code "89") (name "unconnected-(U3-NC-Pad22)") (class "Default")
      (node (ref "U3") (pin "22") (pinfunction "NC_22") (pintype "passive"))
    )
    (net (code "90") (name "unconnected-(U3-RI-Pad2)") (class "Default")
      (node (ref "U3") (pin "2") (pinfunction "RI_2") (pintype "passive"))
    )
    (net (code "91") (name "unconnected-(U3-RTS-Pad24)") (class "Default")
      (node (ref "U3") (pin "24") (pinfunction "RTS_24") (pintype "passive"))
    )
    (net (code "92") (name "unconnected-(U3-SUSPEND-Pad12)") (class "Default")
      (node (ref "U3") (pin "12") (pinfunction "SUSPEND_12") (pintype "passive"))
    )
    (net (code "93") (name "unconnected-(U3-VDD-Pad6)") (class "Default")
      (node (ref "U3") (pin "6") (pinfunction "VDD_6") (pintype "passive"))
    )
    (net (code "94") (name "unconnected-(U4-CPEN-Pad3)") (class "Default")
      (node (ref "U4") (pin "3") (pinfunction "CPEN_3") (pintype "output+no_connect"))
    )
    (net (code "95") (name "unconnected-(U4-EXTVBUS-Pad10)") (class "Default")
      (node (ref "U4") (pin "10") (pinfunction "EXTVBUS_10") (pintype "input+no_connect"))
    )
    (net (code "96") (name "unconnected-(U4-ID-Pad5)") (class "Default")
      (node (ref "U4") (pin "5") (pinfunction "ID_5") (pintype "input+no_connect"))
    )
  )
)
